# LED_Tutorial_2.net
KiCad netlist of a schematic drawn in Altium Designer
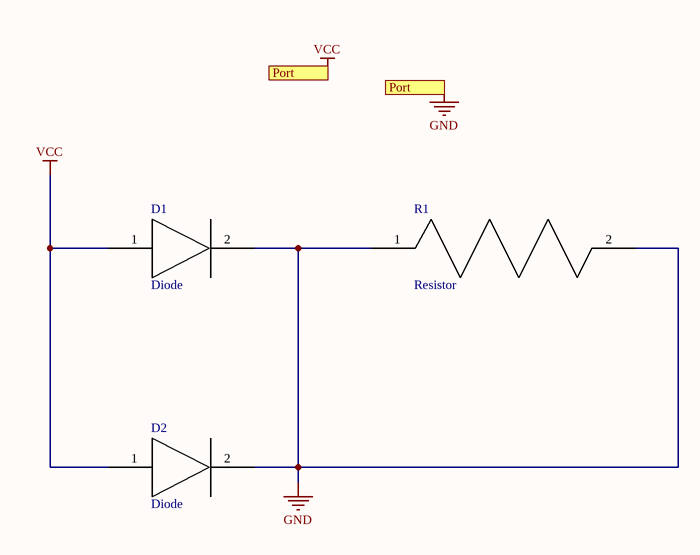
[diagram p0: LED_Tutorial_2.SchDoc]

(export (version "E")
  (design (tool "Eeschema 10.0.6"))
  (components
    (comp (ref "D1") (value "Diode") (libsource (lib "LED_Tutorial_2") (part "Diode")))
    (comp (ref "D2") (value "Diode") (libsource (lib "LED_Tutorial_2") (part "Diode")))
    (comp (ref "R1") (value "Resistor") (libsource (lib "LED_Tutorial_2") (part "Resistor")))
  )
  (nets
    (net (code "1") (name "GND") (class "Default")
      (node (ref "D1") (pin "1") (pinfunction "1_1") (pintype "passive"))
      (node (ref "D1") (pin "2") (pinfunction "2_2") (pintype "passive"))
      (node (ref "D2") (pin "1") (pinfunction "1_1") (pintype "passive"))
      (node (ref "D2") (pin "2") (pinfunction "2_2") (pintype "passive"))
      (node (ref "R1") (pin "1") (pinfunction "1_1") (pintype "passive"))
      (node (ref "R1") (pin "2") (pinfunction "2_2") (pintype "passive"))
    )
  )
)
